# MouseGoggles_MiniBrdAA-1-0.net
KiCad netlist of a schematic drawn in EAGLE
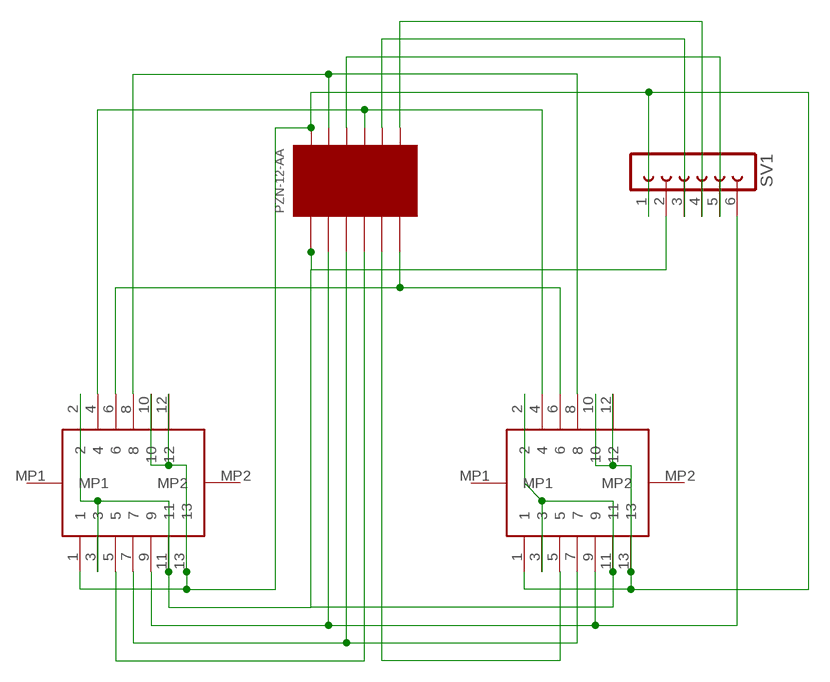
[diagram p0: schematic, sheet 1]

(export (version "E")
  (design (tool "Eeschema 10.0.6"))
  (components
    (comp (ref "J1")
      (value "1-2328724-3")
      (footprint "eagle-import:123287243")
      (fields (field (name "MOUSER_PART_NUMBER") "571-1-2328724-3"))
      (libsource (lib "eagle-import") (part "1-2328724-3"))
    )
    (comp (ref "J2")
      (value "1-2328724-3")
      (footprint "eagle-import:123287243")
      (fields (field (name "MOUSER_PART_NUMBER") "571-1-2328724-3"))
      (libsource (lib "eagle-import") (part "1-2328724-3"))
    )
    (comp (ref "SV1")
      (value "FE06-1")
      (footprint "eagle-import:FE06")
      (libsource (lib "eagle-import") (part "FE06-1"))
    )
    (comp (ref "U$1")
      (value "PZN_12_AA")
      (footprint "eagle-import:OMN_PZN_NANO_6X2")
      (libsource (lib "eagle-import") (part "PZN_12_AA"))
    )
  )
  (nets
    (net (code "1") (name "Net-(U$1-1)") (class "Default")
      (node (ref "J1") (pin "1") (pinfunction "1_1") (pintype "bidirectional"))
      (node (ref "J1") (pin "10") (pinfunction "10_10") (pintype "bidirectional"))
      (node (ref "J1") (pin "12") (pinfunction "12_12") (pintype "bidirectional"))
      (node (ref "J1") (pin "13") (pinfunction "13_13") (pintype "bidirectional"))
      (node (ref "J2") (pin "1") (pinfunction "1_1") (pintype "bidirectional"))
      (node (ref "J2") (pin "10") (pinfunction "10_10") (pintype "bidirectional"))
      (node (ref "J2") (pin "12") (pinfunction "12_12") (pintype "bidirectional"))
      (node (ref "J2") (pin "13") (pinfunction "13_13") (pintype "bidirectional"))
      (node (ref "SV1") (pin "1") (pinfunction "1_1") (pintype "passive"))
      (node (ref "U$1") (pin "P$1") (pinfunction "1_P$1") (pintype "bidirectional"))
    )
    (net (code "2") (name "Net-(U$1-2)") (class "Default")
      (node (ref "J1") (pin "11") (pinfunction "11_11") (pintype "bidirectional"))
      (node (ref "J1") (pin "2") (pinfunction "2_2") (pintype "bidirectional"))
      (node (ref "J1") (pin "3") (pinfunction "3_3") (pintype "bidirectional"))
      (node (ref "J2") (pin "11") (pinfunction "11_11") (pintype "bidirectional"))
      (node (ref "J2") (pin "2") (pinfunction "2_2") (pintype "bidirectional"))
      (node (ref "J2") (pin "3") (pinfunction "3_3") (pintype "bidirectional"))
      (node (ref "SV1") (pin "2") (pinfunction "2_2") (pintype "passive"))
      (node (ref "U$1") (pin "P$2") (pinfunction "2_P$2") (pintype "bidirectional"))
    )
    (net (code "3") (name "Net-(U$1-3)") (class "Default")
      (node (ref "J1") (pin "8") (pinfunction "8_8") (pintype "bidirectional"))
      (node (ref "J2") (pin "8") (pinfunction "8_8") (pintype "bidirectional"))
      (node (ref "U$1") (pin "P$3") (pinfunction "3_P$3") (pintype "bidirectional"))
    )
    (net (code "4") (name "Net-(U$1-4)") (class "Default")
      (node (ref "J1") (pin "9") (pinfunction "9_9") (pintype "bidirectional"))
      (node (ref "J2") (pin "9") (pinfunction "9_9") (pintype "bidirectional"))
      (node (ref "SV1") (pin "6") (pinfunction "6_6") (pintype "passive"))
      (node (ref "U$1") (pin "P$4") (pinfunction "4_P$4") (pintype "bidirectional"))
    )
    (net (code "5") (name "Net-(U$1-5)") (class "Default")
      (node (ref "SV1") (pin "5") (pinfunction "5_5") (pintype "passive"))
      (node (ref "U$1") (pin "P$5") (pinfunction "5_P$5") (pintype "bidirectional"))
    )
    (net (code "6") (name "Net-(U$1-6)") (class "Default")
      (node (ref "J1") (pin "7") (pinfunction "7_7") (pintype "bidirectional"))
      (node (ref "J2") (pin "7") (pinfunction "7_7") (pintype "bidirectional"))
      (node (ref "U$1") (pin "P$6") (pinfunction "6_P$6") (pintype "bidirectional"))
    )
    (net (code "7") (name "Net-(U$1-7)") (class "Default")
      (node (ref "J1") (pin "4") (pinfunction "4_4") (pintype "bidirectional"))
      (node (ref "J2") (pin "4") (pinfunction "4_4") (pintype "bidirectional"))
      (node (ref "U$1") (pin "P$7") (pinfunction "7_P$7") (pintype "bidirectional"))
    )
    (net (code "8") (name "Net-(U$1-8)") (class "Default")
      (node (ref "J1") (pin "5") (pinfunction "5_5") (pintype "bidirectional"))
      (node (ref "U$1") (pin "P$8") (pinfunction "8_P$8") (pintype "bidirectional"))
    )
    (net (code "9") (name "Net-(U$1-9)") (class "Default")
      (node (ref "SV1") (pin "3") (pinfunction "3_3") (pintype "passive"))
      (node (ref "U$1") (pin "P$9") (pinfunction "9_P$9") (pintype "bidirectional"))
    )
    (net (code "10") (name "Net-(U$1-10)") (class "Default")
      (node (ref "J2") (pin "5") (pinfunction "5_5") (pintype "bidirectional"))
      (node (ref "U$1") (pin "P$10") (pinfunction "10_P$10") (pintype "bidirectional"))
    )
    (net (code "11") (name "Net-(U$1-11)") (class "Default")
      (node (ref "SV1") (pin "4") (pinfunction "4_4") (pintype "passive"))
      (node (ref "U$1") (pin "P$11") (pinfunction "11_P$11") (pintype "bidirectional"))
    )
    (net (code "12") (name "Net-(U$1-12)") (class "Default")
      (node (ref "J1") (pin "6") (pinfunction "6_6") (pintype "bidirectional"))
      (node (ref "J2") (pin "6") (pinfunction "6_6") (pintype "bidirectional"))
      (node (ref "U$1") (pin "P$12") (pinfunction "12_P$12") (pintype "bidirectional"))
    )
    (net (code "13") (name "unconnected-(J1-PadMP1)") (class "Default")
      (node (ref "J1") (pin "MP1") (pinfunction "MP1_MP1") (pintype "bidirectional"))
    )
    (net (code "14") (name "unconnected-(J1-PadMP2)") (class "Default")
      (node (ref "J1") (pin "MP2") (pinfunction "MP2_MP2") (pintype "bidirectional"))
    )
    (net (code "15") (name "unconnected-(J2-PadMP1)") (class "Default")
      (node (ref "J2") (pin "MP1") (pinfunction "MP1_MP1") (pintype "bidirectional"))
    )
    (net (code "16") (name "unconnected-(J2-PadMP2)") (class "Default")
      (node (ref "J2") (pin "MP2") (pinfunction "MP2_MP2") (pintype "bidirectional"))
    )
  )
)
